# MCU.net
KiCad netlist of a schematic drawn in Altium Designer
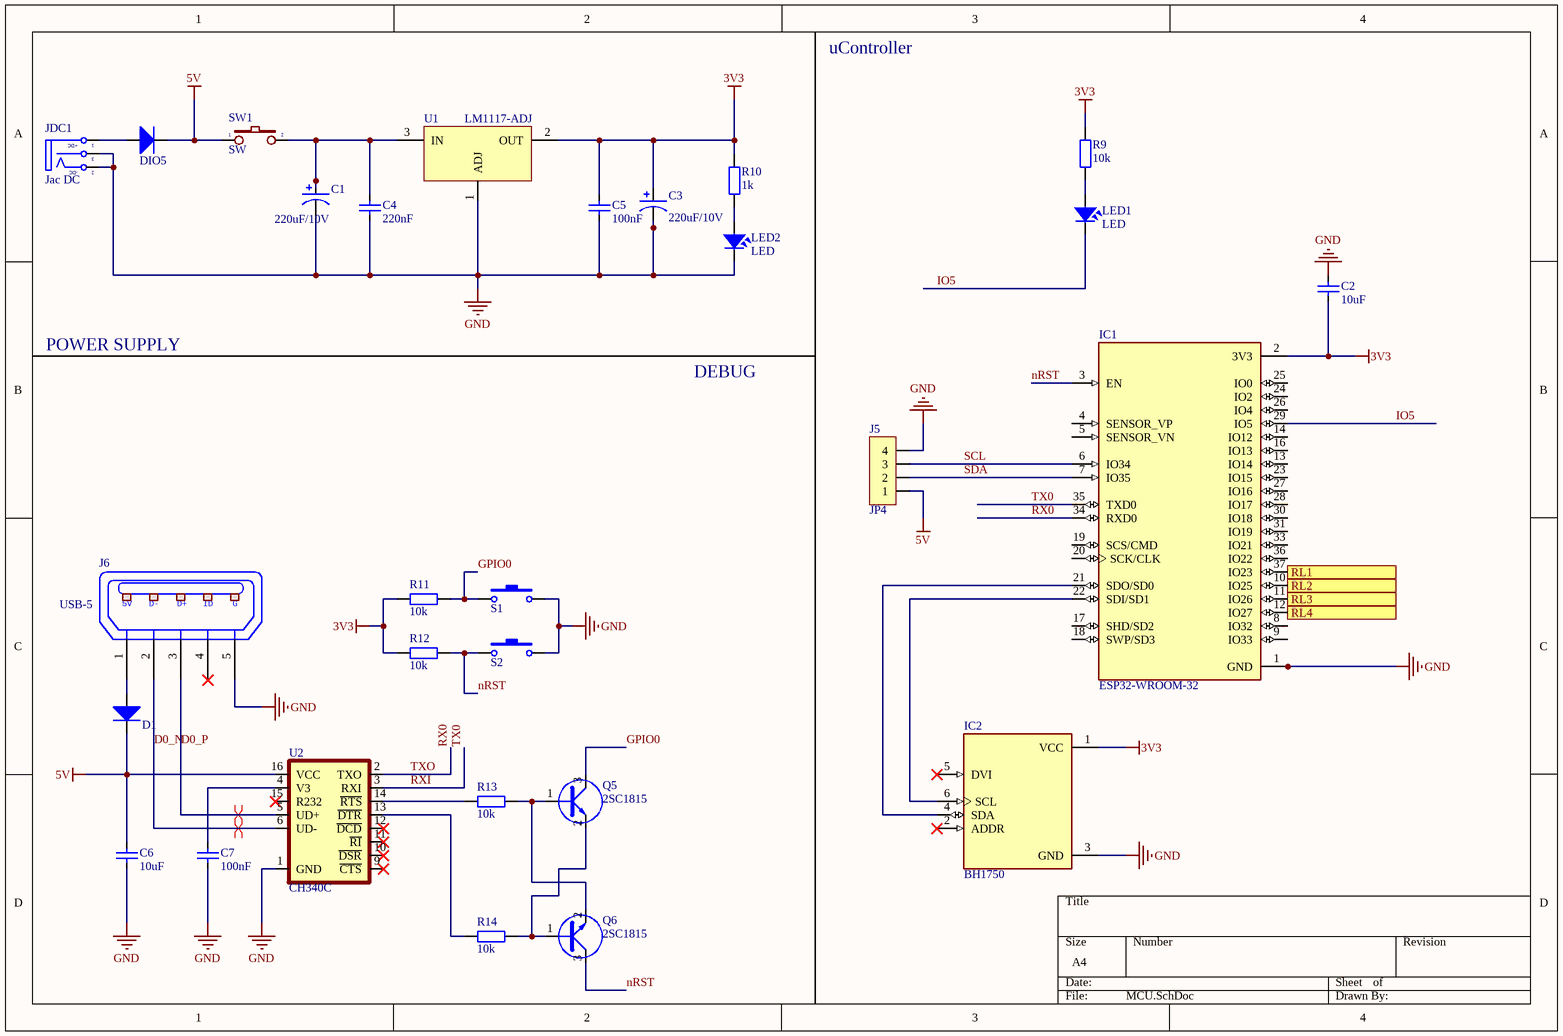
[diagram p0: MCU.SchDoc]

(export (version "E")
  (design (tool "Eeschema 10.0.6"))
  (components
    (comp (ref "C1")
      (value "220uF/10V")
      (footprint "C5mm")
      (description "Polarized Capacitor (Axial)")
      (fields (field (name "PUBLISHER") "Altium Limited"))
      (libsource (lib "Ven_lib") (part "Cap Pol"))
    )
    (comp (ref "C2")
      (value "10uF")
      (footprint "CAP_0805")
      (description "Capacitor")
      (fields (field (name "PUBLISHER") "Altium Limited"))
      (libsource (lib "My Library") (part "CapSMD"))
    )
    (comp (ref "C3")
      (value "220uF/10V")
      (footprint "C5mm")
      (description "Polarized Capacitor (Axial)")
      (fields (field (name "PUBLISHER") "Altium Limited"))
      (libsource (lib "Ven_lib") (part "Cap Pol"))
    )
    (comp (ref "C4")
      (value "220nF")
      (footprint "CAP_0805")
      (description "Capacitor")
      (fields (field (name "PUBLISHER") "Altium Limited"))
      (libsource (lib "My Library") (part "CapSMD"))
    )
    (comp (ref "C5")
      (value "100nF")
      (footprint "CAP_0805")
      (description "Capacitor")
      (fields (field (name "PUBLISHER") "Altium Limited"))
      (libsource (lib "My Library") (part "CapSMD"))
    )
    (comp (ref "C6")
      (value "10uF")
      (footprint "CAP_0805")
      (description "Capacitor")
      (fields (field (name "PUBLISHER") "Altium Limited"))
      (libsource (lib "My Library") (part "CapSMD"))
    )
    (comp (ref "C7")
      (value "100nF")
      (footprint "CAP_0805")
      (description "Capacitor")
      (fields (field (name "PUBLISHER") "Altium Limited"))
      (libsource (lib "My Library") (part "CapSMD"))
    )
    (comp (ref "D1")
      (value "Diode SMD")
      (footprint "DIO-214AC(SMA)")
      (description "Default Diode")
      (fields (field (name "PUBLISHER") "Altium Limited"))
      (libsource (lib "My Library") (part "Diode SMD"))
    )
    (comp (ref "DIO5")
      (value "Diode SMD")
      (footprint "DIO-214AC(SMA)")
      (description "Default Diode")
      (fields (field (name "PUBLISHER") "Altium Limited"))
      (libsource (lib "My Library") (part "Diode SMD"))
    )
    (comp (ref "IC1")
      (value "ESP32-WROOM-32")
      (footprint "MODULE_ESP32-WROOM-32")
      (description "Bluetooth, WiFi Transceiver Module 2.4GHz ~ 2.5GHz Surface Mount")
      (fields (field (name "MF") "Espressif Systems") (field (name "DIGI-KEY_PART_NUMBER") "1904-1010-1-ND"))
      (libsource (lib "Ven_lib") (part "ESP32-WROOM-32"))
    )
    (comp (ref "IC2") (value "BH1750") (footprint "BH1750") (libsource (lib "Ven_lib") (part "BH1750")))
    (comp (ref "J5")
      (value "JP4")
      (footprint "JP4-C1T")
      (description "WR-PHD 2.54 mm Angled Socket Header")
      (fields
        (field (name "MANUFACTURER") "Würth Elektronik eiSos GmbH")
        (field (name "PARTNO") "613004143121")
        (field (name "CREATED BY") "Karrer Zheng")
      )
      (libsource (lib "My Library") (part "JP4"))
    )
    (comp (ref "J6")
      (value "USB-5")
      (footprint "USB-M1")
      (fields
        (field (name "MANUFACTURER") "FCI")
        (field (name "MANUFACTURER PART NUMBER") "10118193-0001LF")
        (field (name ".CREATOR") "MM")
        (field (name ".CHECKED PCB") "RF")
        (field (name ".CHECKED SCH") "MM")
      )
      (libsource (lib "My Library") (part "USB-5"))
    )
    (comp (ref "JDC1")
      (value "Jac DC")
      (footprint "DC-IN")
      (description "Jac DC input")
      (libsource (lib "My Library") (part "DCIN"))
    )
    (comp (ref "LED1")
      (value "LED")
      (footprint "LED-0805-Orange")
      (description "LED Single colour Green and Red")
      (libsource (lib "My Library") (part "LED"))
    )
    (comp (ref "LED2")
      (value "LED")
      (footprint "LED-0805-Red")
      (description "LED Single colour Green and Red")
      (libsource (lib "My Library") (part "LED"))
    )
    (comp (ref "Q5")
      (value "2SC1815")
      (footprint "SOT23D")
      (description "NPN 600mW, ECB")
      (libsource (lib "My Library") (part "C1815"))
    )
    (comp (ref "Q6")
      (value "2SC1815")
      (footprint "SOT23D")
      (description "NPN 600mW, ECB")
      (libsource (lib "") (part "C1815_1"))
    )
    (comp (ref "R9")
      (value "10k")
      (footprint "RES-SMD-0805")
      (description "Resistor SMD")
      (fields
        (field (name "MANUFACTURER") "Generic Components")
        (field (name "PUBLISHER") "Altium Hobart Technology Centre")
      )
      (libsource (lib "My Library") (part "Resistor - SMD"))
    )
    (comp (ref "R10")
      (value "1k")
      (footprint "RES-SMD-0805")
      (description "Resistor SMD")
      (fields
        (field (name "MANUFACTURER") "Generic Components")
        (field (name "PUBLISHER") "Altium Hobart Technology Centre")
      )
      (libsource (lib "My Library") (part "Resistor - SMD"))
    )
    (comp (ref "R11")
      (value "10k")
      (footprint "RES-SMD-0805")
      (description "Resistor SMD")
      (fields
        (field (name "MANUFACTURER") "Generic Components")
        (field (name "PUBLISHER") "Altium Hobart Technology Centre")
      )
      (libsource (lib "My Library") (part "Resistor - SMD"))
    )
    (comp (ref "R12")
      (value "10k")
      (footprint "RES-SMD-0805")
      (description "Resistor SMD")
      (fields
        (field (name "MANUFACTURER") "Generic Components")
        (field (name "PUBLISHER") "Altium Hobart Technology Centre")
      )
      (libsource (lib "My Library") (part "Resistor - SMD"))
    )
    (comp (ref "R13")
      (value "10k")
      (footprint "RES-SMD-0805")
      (description "Resistor SMD")
      (fields
        (field (name "MANUFACTURER") "Generic Components")
        (field (name "PUBLISHER") "Altium Hobart Technology Centre")
      )
      (libsource (lib "My Library") (part "Resistor - SMD"))
    )
    (comp (ref "R14")
      (value "10k")
      (footprint "RES-SMD-0805")
      (description "Resistor SMD")
      (fields
        (field (name "MANUFACTURER") "Generic Components")
        (field (name "PUBLISHER") "Altium Hobart Technology Centre")
      )
      (libsource (lib "My Library") (part "Resistor - SMD"))
    )
    (comp (ref "S1")
      (value "SW-SMD")
      (footprint "SW 3x2x4")
      (description "Switch")
      (fields (field (name "PUBLISHER") "Altium Limited"))
      (libsource (lib "My Library") (part "SW-SMD"))
    )
    (comp (ref "S2")
      (value "SW-SMD")
      (footprint "SW 3x2x4")
      (description "Switch")
      (fields (field (name "PUBLISHER") "Altium Limited"))
      (libsource (lib "My Library") (part "SW-SMD"))
    )
    (comp (ref "SW1")
      (value "SW")
      (footprint "SW2")
      (description "Switch button 2 pin")
      (libsource (lib "My Library") (part "SW2"))
    )
    (comp (ref "U1")
      (value "LM1117-ADJ")
      (footprint "LM1117-SOP")
      (description "800mA Low-Dropout Linear Regulator")
      (fields (field (name "CREATOR") "Nguyen Ba Bien"))
      (libsource (lib "My Library") (part "LM1117-ADJ"))
    )
    (comp (ref "U2")
      (value "CH340C")
      (footprint "SOP-16")
      (description "USB to serial chip CH340")
      (fields (field (name "MF") "WCH"))
      (libsource (lib "My Library") (part "CH340C"))
    )
  )
  (nets
    (net (code "1") (name "/D0_N") (class "Default")
      (node (ref "J6") (pin "2") (pinfunction "P2_2") (pintype "passive"))
      (node (ref "U2") (pin "6") (pinfunction "UD-_6") (pintype "bidirectional"))
    )
    (net (code "2") (name "/D0_P") (class "Default")
      (node (ref "J6") (pin "3") (pinfunction "P3_3") (pintype "passive"))
      (node (ref "U2") (pin "5") (pinfunction "UD+_5") (pintype "bidirectional"))
    )
    (net (code "3") (name "/GPIO0") (class "Default")
      (node (ref "Q5") (pin "3") (pinfunction "C_3") (pintype "passive"))
      (node (ref "R11") (pin "1") (pinfunction "1_1") (pintype "passive"))
      (node (ref "S1") (pin "1") (pinfunction "1_1") (pintype "passive"))
    )
    (net (code "4") (name "/IO5") (class "Default")
      (node (ref "IC1") (pin "29") (pinfunction "IO5_29") (pintype "bidirectional"))
      (node (ref "LED1") (pin "2") (pinfunction "2_2") (pintype "passive"))
    )
    (net (code "5") (name "/RL1") (class "Default")
      (node (ref "IC1") (pin "37") (pinfunction "IO23_37") (pintype "bidirectional"))
    )
    (net (code "6") (name "/RL2") (class "Default")
      (node (ref "IC1") (pin "10") (pinfunction "IO25_10") (pintype "bidirectional"))
    )
    (net (code "7") (name "/RL3") (class "Default")
      (node (ref "IC1") (pin "11") (pinfunction "IO26_11") (pintype "bidirectional"))
    )
    (net (code "8") (name "/RL4") (class "Default")
      (node (ref "IC1") (pin "12") (pinfunction "IO27_12") (pintype "bidirectional"))
    )
    (net (code "9") (name "/RX0") (class "Default")
      (node (ref "IC1") (pin "34") (pinfunction "RXD0_34") (pintype "bidirectional"))
      (node (ref "U2") (pin "2") (pinfunction "TXO_2") (pintype "bidirectional"))
    )
    (net (code "10") (name "/RXI") (class "Default")
      (node (ref "IC1") (pin "35") (pinfunction "TXD0_35") (pintype "bidirectional"))
      (node (ref "U2") (pin "3") (pinfunction "RXI_3") (pintype "bidirectional"))
    )
    (net (code "11") (name "/SCL") (class "Default")
      (node (ref "IC1") (pin "6") (pinfunction "IO34_6") (pintype "input"))
      (node (ref "J5") (pin "3") (pinfunction "3_3") (pintype "passive"))
    )
    (net (code "12") (name "/SDA") (class "Default")
      (node (ref "IC1") (pin "7") (pinfunction "IO35_7") (pintype "input"))
      (node (ref "J5") (pin "2") (pinfunction "2_2") (pintype "passive"))
    )
    (net (code "13") (name "/nRST") (class "Default")
      (node (ref "IC1") (pin "3") (pinfunction "EN_3") (pintype "input"))
      (node (ref "Q6") (pin "3") (pinfunction "C_3") (pintype "passive"))
      (node (ref "R12") (pin "1") (pinfunction "1_1") (pintype "passive"))
      (node (ref "S2") (pin "1") (pinfunction "1_1") (pintype "passive"))
    )
    (net (code "14") (name "3V3") (class "Default")
      (node (ref "C2") (pin "2") (pinfunction "2_2") (pintype "passive"))
      (node (ref "C3") (pin "1") (pinfunction "1_1") (pintype "passive"))
      (node (ref "C5") (pin "2") (pinfunction "2_2") (pintype "passive"))
      (node (ref "IC1") (pin "2") (pinfunction "3V3_2") (pintype "power_in"))
      (node (ref "IC2") (pin "1") (pinfunction "VCC_1") (pintype "power_in"))
      (node (ref "R10") (pin "1") (pinfunction "1_1") (pintype "passive"))
      (node (ref "R11") (pin "2") (pinfunction "2_2") (pintype "passive"))
      (node (ref "R12") (pin "2") (pinfunction "2_2") (pintype "passive"))
      (node (ref "R9") (pin "1") (pinfunction "1_1") (pintype "passive"))
      (node (ref "U1") (pin "2") (pinfunction "OUT_2") (pintype "passive"))
    )
    (net (code "15") (name "5V") (class "Default")
      (node (ref "C6") (pin "2") (pinfunction "2_2") (pintype "passive"))
      (node (ref "D1") (pin "2") (pinfunction "K_2") (pintype "passive"))
      (node (ref "DIO5") (pin "2") (pinfunction "K_2") (pintype "passive"))
      (node (ref "J5") (pin "1") (pinfunction "1_1") (pintype "passive"))
      (node (ref "SW1") (pin "1") (pinfunction "1_1") (pintype "passive"))
      (node (ref "U2") (pin "16") (pinfunction "VCC_16") (pintype "bidirectional"))
    )
    (net (code "16") (name "GND") (class "Default")
      (node (ref "C1") (pin "2") (pinfunction "2_2") (pintype "passive"))
      (node (ref "C2") (pin "1") (pinfunction "1_1") (pintype "passive"))
      (node (ref "C3") (pin "2") (pinfunction "2_2") (pintype "passive"))
      (node (ref "C4") (pin "1") (pinfunction "1_1") (pintype "passive"))
      (node (ref "C5") (pin "1") (pinfunction "1_1") (pintype "passive"))
      (node (ref "C6") (pin "1") (pinfunction "1_1") (pintype "passive"))
      (node (ref "C7") (pin "1") (pinfunction "1_1") (pintype "passive"))
      (node (ref "IC1") (pin "1") (pinfunction "GND_1") (pintype "power_in"))
      (node (ref "IC1") (pin "15") (pinfunction "GND_15") (pintype "power_in"))
      (node (ref "IC1") (pin "38") (pinfunction "GND_38") (pintype "power_in"))
      (node (ref "IC1") (pin "39_1") (pinfunction "GND_39_1") (pintype "power_in"))
      (node (ref "IC1") (pin "39_10") (pinfunction "GND_39_10") (pintype "power_in"))
      (node (ref "IC1") (pin "39_11") (pinfunction "GND_39_11") (pintype "power_in"))
      (node (ref "IC1") (pin "39_12") (pinfunction "GND_39_12") (pintype "power_in"))
      (node (ref "IC1") (pin "39_13") (pinfunction "GND_39_13") (pintype "power_in"))
      (node (ref "IC1") (pin "39_14") (pinfunction "GND_39_14") (pintype "power_in"))
      (node (ref "IC1") (pin "39_15") (pinfunction "GND_39_15") (pintype "power_in"))
      (node (ref "IC1") (pin "39_16") (pinfunction "GND_39_16") (pintype "power_in"))
      (node (ref "IC1") (pin "39_17") (pinfunction "GND_39_17") (pintype "power_in"))
      (node (ref "IC1") (pin "39_18") (pinfunction "GND_39_18") (pintype "power_in"))
      (node (ref "IC1") (pin "39_19") (pinfunction "GND_39_19") (pintype "power_in"))
      (node (ref "IC1") (pin "39_2") (pinfunction "GND_39_2") (pintype "power_in"))
      (node (ref "IC1") (pin "39_20") (pinfunction "GND_39_20") (pintype "power_in"))
      (node (ref "IC1") (pin "39_21") (pinfunction "GND_39_21") (pintype "power_in"))
      (node (ref "IC1") (pin "39_3") (pinfunction "GND_39_3") (pintype "power_in"))
      (node (ref "IC1") (pin "39_4") (pinfunction "GND_39_4") (pintype "power_in"))
      (node (ref "IC1") (pin "39_5") (pinfunction "GND_39_5") (pintype "power_in"))
      (node (ref "IC1") (pin "39_6") (pinfunction "GND_39_6") (pintype "power_in"))
      (node (ref "IC1") (pin "39_7") (pinfunction "GND_39_7") (pintype "power_in"))
      (node (ref "IC1") (pin "39_8") (pinfunction "GND_39_8") (pintype "power_in"))
      (node (ref "IC1") (pin "39_9") (pinfunction "GND_39_9") (pintype "power_in"))
      (node (ref "IC2") (pin "3") (pinfunction "GND_3") (pintype "power_in"))
      (node (ref "J5") (pin "4") (pinfunction "4_4") (pintype "passive"))
      (node (ref "J6") (pin "5") (pinfunction "P5_5") (pintype "passive"))
      (node (ref "JDC1") (pin "2") (pinfunction "TN_2") (pintype "passive"))
      (node (ref "JDC1") (pin "3") (pinfunction "S_3") (pintype "power_in"))
      (node (ref "LED2") (pin "2") (pinfunction "2_2") (pintype "passive"))
      (node (ref "S1") (pin "2") (pinfunction "2_2") (pintype "passive"))
      (node (ref "S2") (pin "2") (pinfunction "2_2") (pintype "passive"))
      (node (ref "U1") (pin "1") (pinfunction "ADJ_1") (pintype "passive"))
      (node (ref "U2") (pin "1") (pinfunction "GND_1") (pintype "bidirectional"))
    )
    (net (code "17") (name "Net-(D1-A)") (class "Default")
      (node (ref "D1") (pin "1") (pinfunction "A_1") (pintype "passive"))
      (node (ref "J6") (pin "1") (pinfunction "P1_1") (pintype "passive"))
    )
    (net (code "18") (name "Net-(DIO5-A)") (class "Default")
      (node (ref "DIO5") (pin "1") (pinfunction "A_1") (pintype "passive"))
      (node (ref "JDC1") (pin "1") (pinfunction "T_1") (pintype "passive"))
    )
    (net (code "19") (name "Net-(IC1-SDI{slash}SD1)") (class "Default")
      (node (ref "IC1") (pin "22") (pinfunction "SDI/SD1_22") (pintype "bidirectional"))
      (node (ref "IC2") (pin "6") (pinfunction "SCL_6") (pintype "input"))
    )
    (net (code "20") (name "Net-(IC1-SDO{slash}SD0)") (class "Default")
      (node (ref "IC1") (pin "21") (pinfunction "SDO/SD0_21") (pintype "bidirectional"))
      (node (ref "IC2") (pin "4") (pinfunction "SDA_4") (pintype "bidirectional"))
    )
    (net (code "21") (name "Net-(LED1-Pad1)") (class "Default")
      (node (ref "LED1") (pin "1") (pinfunction "1_1") (pintype "passive"))
      (node (ref "R9") (pin "2") (pinfunction "2_2") (pintype "passive"))
    )
    (net (code "22") (name "Net-(LED2-Pad1)") (class "Default")
      (node (ref "LED2") (pin "1") (pinfunction "1_1") (pintype "passive"))
      (node (ref "R10") (pin "2") (pinfunction "2_2") (pintype "passive"))
    )
    (net (code "23") (name "Net-(Q5-B)") (class "Default")
      (node (ref "Q5") (pin "1") (pinfunction "B_1") (pintype "passive"))
      (node (ref "Q6") (pin "2") (pinfunction "E_2") (pintype "passive"))
      (node (ref "R13") (pin "1") (pinfunction "1_1") (pintype "passive"))
    )
    (net (code "24") (name "Net-(Q5-E)") (class "Default")
      (node (ref "Q5") (pin "2") (pinfunction "E_2") (pintype "passive"))
      (node (ref "Q6") (pin "1") (pinfunction "B_1") (pintype "passive"))
      (node (ref "R14") (pin "1") (pinfunction "1_1") (pintype "passive"))
    )
    (net (code "25") (name "Net-(U1-IN)") (class "Default")
      (node (ref "C1") (pin "1") (pinfunction "1_1") (pintype "passive"))
      (node (ref "C4") (pin "2") (pinfunction "2_2") (pintype "passive"))
      (node (ref "SW1") (pin "2") (pinfunction "2_2") (pintype "passive"))
      (node (ref "U1") (pin "3") (pinfunction "IN_3") (pintype "passive"))
    )
    (net (code "26") (name "Net-(U2-V3)") (class "Default")
      (node (ref "C7") (pin "2") (pinfunction "2_2") (pintype "passive"))
      (node (ref "U2") (pin "4") (pinfunction "V3_4") (pintype "bidirectional"))
    )
    (net (code "27") (name "Net-(U2-~{DTR})") (class "Default")
      (node (ref "R14") (pin "2") (pinfunction "2_2") (pintype "passive"))
      (node (ref "U2") (pin "13") (pinfunction "~{DTR}_13") (pintype "bidirectional"))
    )
    (net (code "28") (name "Net-(U2-~{RTS})") (class "Default")
      (node (ref "R13") (pin "2") (pinfunction "2_2") (pintype "passive"))
      (node (ref "U2") (pin "14") (pinfunction "~{RTS}_14") (pintype "bidirectional"))
    )
    (net (code "29") (name "unconnected-(IC1-IO0-Pad25)") (class "Default")
      (node (ref "IC1") (pin "25") (pinfunction "IO0_25") (pintype "bidirectional"))
    )
    (net (code "30") (name "unconnected-(IC1-IO2-Pad24)") (class "Default")
      (node (ref "IC1") (pin "24") (pinfunction "IO2_24") (pintype "bidirectional"))
    )
    (net (code "31") (name "unconnected-(IC1-IO4-Pad26)") (class "Default")
      (node (ref "IC1") (pin "26") (pinfunction "IO4_26") (pintype "bidirectional"))
    )
    (net (code "32") (name "unconnected-(IC1-IO12-Pad14)") (class "Default")
      (node (ref "IC1") (pin "14") (pinfunction "IO12_14") (pintype "bidirectional"))
    )
    (net (code "33") (name "unconnected-(IC1-IO13-Pad16)") (class "Default")
      (node (ref "IC1") (pin "16") (pinfunction "IO13_16") (pintype "bidirectional"))
    )
    (net (code "34") (name "unconnected-(IC1-IO14-Pad13)") (class "Default")
      (node (ref "IC1") (pin "13") (pinfunction "IO14_13") (pintype "bidirectional"))
    )
    (net (code "35") (name "unconnected-(IC1-IO15-Pad23)") (class "Default")
      (node (ref "IC1") (pin "23") (pinfunction "IO15_23") (pintype "bidirectional"))
    )
    (net (code "36") (name "unconnected-(IC1-IO16-Pad27)") (class "Default")
      (node (ref "IC1") (pin "27") (pinfunction "IO16_27") (pintype "bidirectional"))
    )
    (net (code "37") (name "unconnected-(IC1-IO17-Pad28)") (class "Default")
      (node (ref "IC1") (pin "28") (pinfunction "IO17_28") (pintype "bidirectional"))
    )
    (net (code "38") (name "unconnected-(IC1-IO18-Pad30)") (class "Default")
      (node (ref "IC1") (pin "30") (pinfunction "IO18_30") (pintype "bidirectional"))
    )
    (net (code "39") (name "unconnected-(IC1-IO19-Pad31)") (class "Default")
      (node (ref "IC1") (pin "31") (pinfunction "IO19_31") (pintype "bidirectional"))
    )
    (net (code "40") (name "unconnected-(IC1-IO21-Pad33)") (class "Default")
      (node (ref "IC1") (pin "33") (pinfunction "IO21_33") (pintype "bidirectional"))
    )
    (net (code "41") (name "unconnected-(IC1-IO22-Pad36)") (class "Default")
      (node (ref "IC1") (pin "36") (pinfunction "IO22_36") (pintype "bidirectional"))
    )
    (net (code "42") (name "unconnected-(IC1-IO32-Pad8)") (class "Default")
      (node (ref "IC1") (pin "8") (pinfunction "IO32_8") (pintype "bidirectional"))
    )
    (net (code "43") (name "unconnected-(IC1-IO33-Pad9)") (class "Default")
      (node (ref "IC1") (pin "9") (pinfunction "IO33_9") (pintype "bidirectional"))
    )
    (net (code "44") (name "unconnected-(IC1-SCK{slash}CLK-Pad20)") (class "Default")
      (node (ref "IC1") (pin "20") (pinfunction "SCK/CLK_20") (pintype "bidirectional"))
    )
    (net (code "45") (name "unconnected-(IC1-SCS{slash}CMD-Pad19)") (class "Default")
      (node (ref "IC1") (pin "19") (pinfunction "SCS/CMD_19") (pintype "bidirectional"))
    )
    (net (code "46") (name "unconnected-(IC1-SENSOR_VN-Pad5)") (class "Default")
      (node (ref "IC1") (pin "5") (pinfunction "SENSOR_VN_5") (pintype "input"))
    )
    (net (code "47") (name "unconnected-(IC1-SENSOR_VP-Pad4)") (class "Default")
      (node (ref "IC1") (pin "4") (pinfunction "SENSOR_VP_4") (pintype "input"))
    )
    (net (code "48") (name "unconnected-(IC1-SHD{slash}SD2-Pad17)") (class "Default")
      (node (ref "IC1") (pin "17") (pinfunction "SHD/SD2_17") (pintype "bidirectional"))
    )
    (net (code "49") (name "unconnected-(IC1-SWP{slash}SD3-Pad18)") (class "Default")
      (node (ref "IC1") (pin "18") (pinfunction "SWP/SD3_18") (pintype "bidirectional"))
    )
    (net (code "50") (name "unconnected-(IC2-ADDR-Pad2)") (class "Default")
      (node (ref "IC2") (pin "2") (pinfunction "ADDR_2") (pintype "input+no_connect"))
    )
    (net (code "51") (name "unconnected-(IC2-DVI-Pad5)") (class "Default")
      (node (ref "IC2") (pin "5") (pinfunction "DVI_5") (pintype "input+no_connect"))
    )
    (net (code "52") (name "unconnected-(J6-P4-Pad4)") (class "Default")
      (node (ref "J6") (pin "4") (pinfunction "P4_4") (pintype "passive+no_connect"))
    )
    (net (code "53") (name "unconnected-(U2-R232-Pad15)") (class "Default")
      (node (ref "U2") (pin "15") (pinfunction "R232_15") (pintype "bidirectional+no_connect"))
    )
    (net (code "54") (name "unconnected-(U2-~{CTS}-Pad9)") (class "Default")
      (node (ref "U2") (pin "9") (pinfunction "~{CTS}_9") (pintype "bidirectional+no_connect"))
    )
    (net (code "55") (name "unconnected-(U2-~{DCD}-Pad12)") (class "Default")
      (node (ref "U2") (pin "12") (pinfunction "~{DCD}_12") (pintype "bidirectional+no_connect"))
    )
    (net (code "56") (name "unconnected-(U2-~{DSR}-Pad10)") (class "Default")
      (node (ref "U2") (pin "10") (pinfunction "~{DSR}_10") (pintype "bidirectional+no_connect"))
    )
    (net (code "57") (name "unconnected-(U2-~{RI}-Pad11)") (class "Default")
      (node (ref "U2") (pin "11") (pinfunction "~{RI}_11") (pintype "bidirectional+no_connect"))
    )
  )
)
